# Test_PCB.net
KiCad netlist of a schematic drawn in Altium Designer
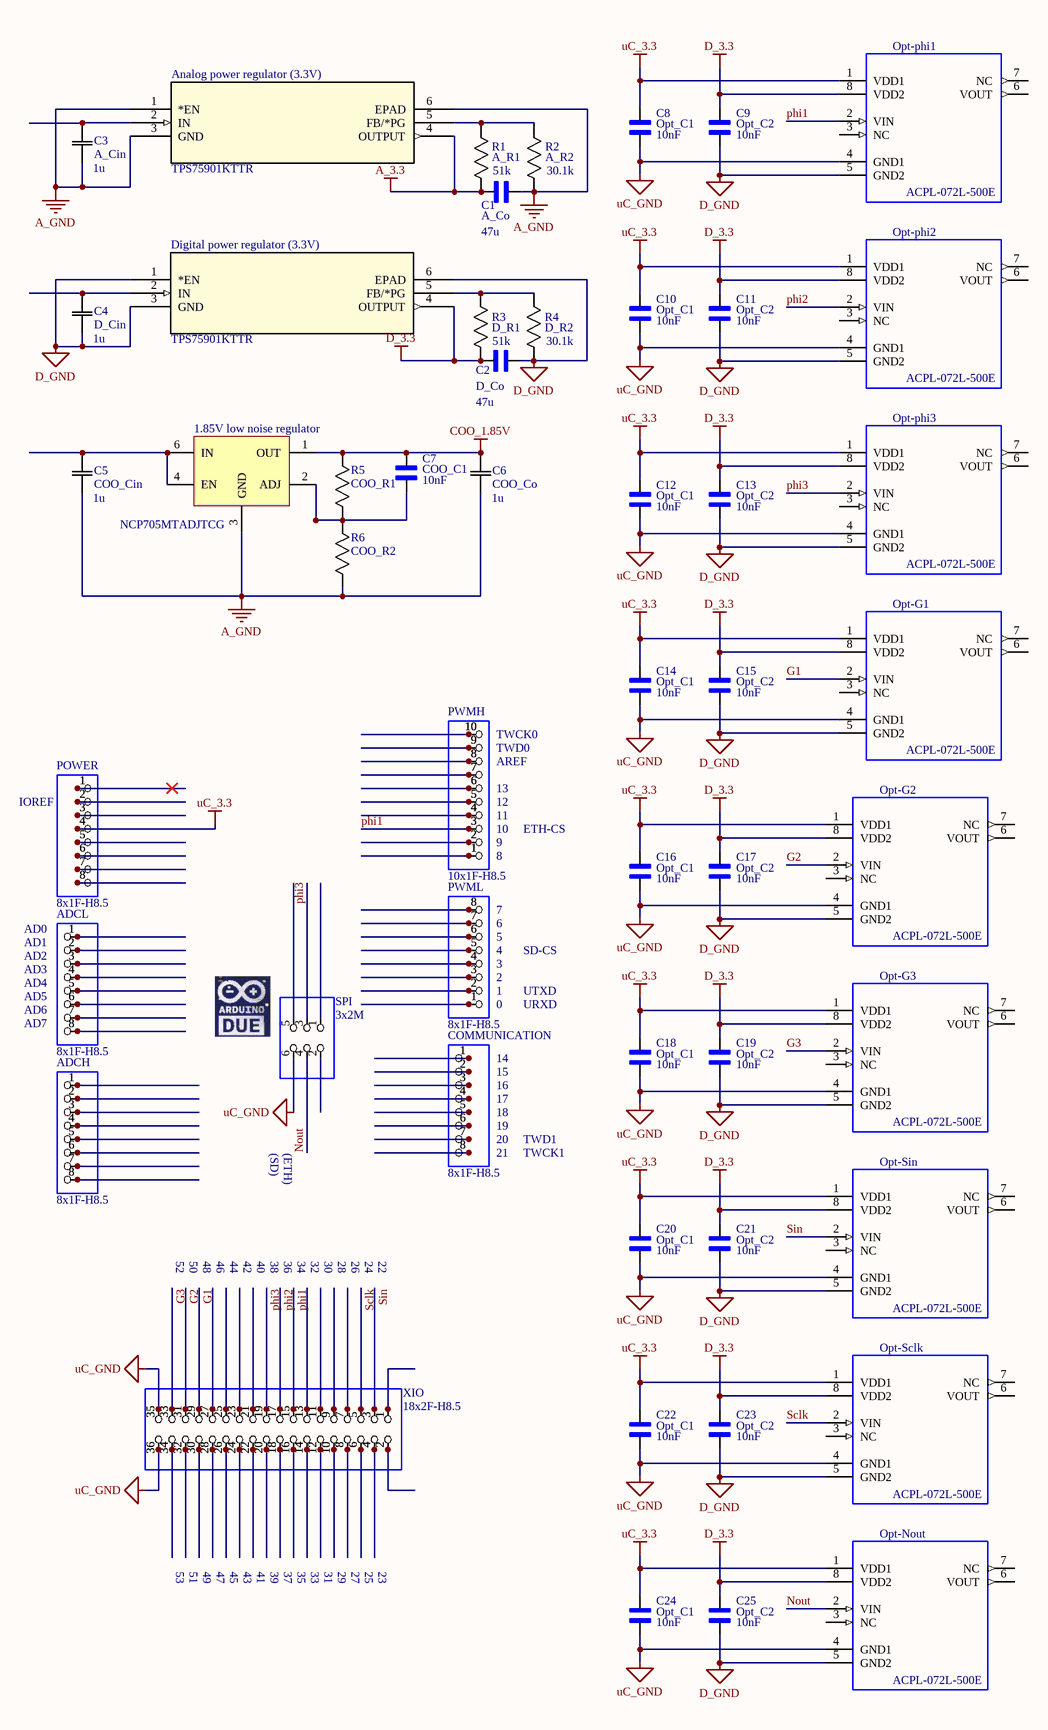
[diagram p0: Test PCB.SchDoc]

(export (version "E")
  (design (tool "Eeschema 10.0.6"))
  (components
    (comp (ref "1.85V low noise regulator")
      (value "NCP705MTADJTCG")
      (footprint "WDFN6")
      (description "500 mA, Ultra-Low  Quiescent Current, IQ 13 A,  Ultra-Low Noise, LDO  Voltage Regulator")
      (fields (field (name "MANUFACTURER") "ON Semiconductor"))
      (libsource (lib "NCP705MTADJTCG") (part "NCP705MTADJTCG"))
    )
    (comp (ref "ADCH") (value "8x1F-H8.5") (footprint "1X08") (libsource (lib "SmartPrj") (part "PINHD-1X8")))
    (comp (ref "ADCL") (value "8x1F-H8.5") (footprint "1X08") (libsource (lib "SmartPrj") (part "PINHD-1X8")))
    (comp (ref "Analog power regulator (3.3V)")
      (value "TPS75901KTTR")
      (footprint "KTT5_6P22X6P86")
      (description "Imported")
      (fields (field (name "MANUFACTURER") "Texas Instruments"))
      (libsource (lib "TPS75901KTTR") (part "TPS75901KTTR"))
    )
    (comp (ref "C1")
      (value "A_Co")
      (footprint "CAPC1608X9N")
      (description "Multilayer Ceramic Capacitors - 47uF 4V X5R 20% Pad SMD 0603 85C T/R")
      (fields
        (field (name "DIGI-KEY_PART_NUMBER") "490-13246-1-ND")
        (field (name "MP") "GRM188R60G476ME15D")
        (field (name "ALTIUM_VALUE") "47u")
      )
      (libsource (lib "47uF 0603  CAP") (part "GRM188R60G476ME15D"))
    )
    (comp (ref "C2")
      (value "D_Co")
      (footprint "CAPC1608X9N")
      (description "Multilayer Ceramic Capacitors - 47uF 4V X5R 20% Pad SMD 0603 85C T/R")
      (fields
        (field (name "DIGI-KEY_PART_NUMBER") "490-13246-1-ND")
        (field (name "MP") "GRM188R60G476ME15D")
        (field (name "ALTIUM_VALUE") "47u")
      )
      (libsource (lib "47uF 0603  CAP") (part "GRM188R60G476ME15D"))
    )
    (comp (ref "C3")
      (value "A_Cin")
      (footprint "CAP_GRM_188")
      (description "Imported")
      (fields
        (field (name "MANUFACTURER_PART_NUMBER") "GRM188R60J105KA01D")
        (field (name "ALTIUM_VALUE") "1u")
      )
      (libsource (lib "1uF 0603 CAP") (part "GRM188R60J105KA0"))
    )
    (comp (ref "C4")
      (value "D_Cin")
      (footprint "CAP_GRM_188")
      (description "Imported")
      (fields
        (field (name "MANUFACTURER_PART_NUMBER") "GRM188R60J105KA01D")
        (field (name "ALTIUM_VALUE") "1u")
      )
      (libsource (lib "1uF 0603 CAP") (part "GRM188R60J105KA0"))
    )
    (comp (ref "C5")
      (value "COO_Cin")
      (footprint "CAP_GRM_188")
      (description "Imported")
      (fields
        (field (name "MANUFACTURER_PART_NUMBER") "GRM188R60J105KA01D")
        (field (name "ALTIUM_VALUE") "1u")
      )
      (libsource (lib "1uF 0603 CAP") (part "GRM188R60J105KA0"))
    )
    (comp (ref "C6")
      (value "COO_Co")
      (footprint "CAP_GRM_188")
      (description "Imported")
      (fields
        (field (name "MANUFACTURER_PART_NUMBER") "GRM188R60J105KA01D")
        (field (name "ALTIUM_VALUE") "1u")
      )
      (libsource (lib "1uF 0603 CAP") (part "GRM188R60J105KA0"))
    )
    (comp (ref "C7")
      (value "COO_C1")
      (footprint "CAPC1608X9N")
      (description "Multilayer Ceramic Capacitor, GRM Series, 0.01 F, 5%, C0G / NP0, 50 V, 0603 [1608 Metric]")
      (fields
        (field (name "MF") "Murata")
        (field (name "DIGI-KEY_PART_NUMBER") "490-9666-1-ND")
        (field (name "ALTIUM_VALUE") "10nF")
      )
      (libsource (lib "10nF 0603 CAP") (part "GRM1885C1H103JA01D"))
    )
    (comp (ref "C8")
      (value "Opt_C1")
      (footprint "CAPC1608X9N")
      (description "Multilayer Ceramic Capacitor, GRM Series, 0.01 F, 5%, C0G / NP0, 50 V, 0603 [1608 Metric]")
      (fields
        (field (name "MF") "Murata")
        (field (name "DIGI-KEY_PART_NUMBER") "490-9666-1-ND")
        (field (name "ALTIUM_VALUE") "10nF")
      )
      (libsource (lib "10nF 0603 CAP") (part "GRM1885C1H103JA01D"))
    )
    (comp (ref "C9")
      (value "Opt_C2")
      (footprint "CAPC1608X9N")
      (description "Multilayer Ceramic Capacitor, GRM Series, 0.01 F, 5%, C0G / NP0, 50 V, 0603 [1608 Metric]")
      (fields
        (field (name "MF") "Murata")
        (field (name "DIGI-KEY_PART_NUMBER") "490-9666-1-ND")
        (field (name "ALTIUM_VALUE") "10nF")
      )
      (libsource (lib "10nF 0603 CAP") (part "GRM1885C1H103JA01D"))
    )
    (comp (ref "C10")
      (value "Opt_C1")
      (footprint "CAPC1608X9N")
      (description "Multilayer Ceramic Capacitor, GRM Series, 0.01 F, 5%, C0G / NP0, 50 V, 0603 [1608 Metric]")
      (fields
        (field (name "MF") "Murata")
        (field (name "DIGI-KEY_PART_NUMBER") "490-9666-1-ND")
        (field (name "ALTIUM_VALUE") "10nF")
      )
      (libsource (lib "10nF 0603 CAP") (part "GRM1885C1H103JA01D"))
    )
    (comp (ref "C11")
      (value "Opt_C2")
      (footprint "CAPC1608X9N")
      (description "Multilayer Ceramic Capacitor, GRM Series, 0.01 F, 5%, C0G / NP0, 50 V, 0603 [1608 Metric]")
      (fields
        (field (name "MF") "Murata")
        (field (name "DIGI-KEY_PART_NUMBER") "490-9666-1-ND")
        (field (name "ALTIUM_VALUE") "10nF")
      )
      (libsource (lib "10nF 0603 CAP") (part "GRM1885C1H103JA01D"))
    )
    (comp (ref "C12")
      (value "Opt_C1")
      (footprint "CAPC1608X9N")
      (description "Multilayer Ceramic Capacitor, GRM Series, 0.01 F, 5%, C0G / NP0, 50 V, 0603 [1608 Metric]")
      (fields
        (field (name "MF") "Murata")
        (field (name "DIGI-KEY_PART_NUMBER") "490-9666-1-ND")
        (field (name "ALTIUM_VALUE") "10nF")
      )
      (libsource (lib "10nF 0603 CAP") (part "GRM1885C1H103JA01D"))
    )
    (comp (ref "C13")
      (value "Opt_C2")
      (footprint "CAPC1608X9N")
      (description "Multilayer Ceramic Capacitor, GRM Series, 0.01 F, 5%, C0G / NP0, 50 V, 0603 [1608 Metric]")
      (fields
        (field (name "MF") "Murata")
        (field (name "DIGI-KEY_PART_NUMBER") "490-9666-1-ND")
        (field (name "ALTIUM_VALUE") "10nF")
      )
      (libsource (lib "10nF 0603 CAP") (part "GRM1885C1H103JA01D"))
    )
    (comp (ref "C14")
      (value "Opt_C1")
      (footprint "CAPC1608X9N")
      (description "Multilayer Ceramic Capacitor, GRM Series, 0.01 F, 5%, C0G / NP0, 50 V, 0603 [1608 Metric]")
      (fields
        (field (name "MF") "Murata")
        (field (name "DIGI-KEY_PART_NUMBER") "490-9666-1-ND")
        (field (name "ALTIUM_VALUE") "10nF")
      )
      (libsource (lib "10nF 0603 CAP") (part "GRM1885C1H103JA01D"))
    )
    (comp (ref "C15")
      (value "Opt_C2")
      (footprint "CAPC1608X9N")
      (description "Multilayer Ceramic Capacitor, GRM Series, 0.01 F, 5%, C0G / NP0, 50 V, 0603 [1608 Metric]")
      (fields
        (field (name "MF") "Murata")
        (field (name "DIGI-KEY_PART_NUMBER") "490-9666-1-ND")
        (field (name "ALTIUM_VALUE") "10nF")
      )
      (libsource (lib "10nF 0603 CAP") (part "GRM1885C1H103JA01D"))
    )
    (comp (ref "C16")
      (value "Opt_C1")
      (footprint "CAPC1608X9N")
      (description "Multilayer Ceramic Capacitor, GRM Series, 0.01 F, 5%, C0G / NP0, 50 V, 0603 [1608 Metric]")
      (fields
        (field (name "MF") "Murata")
        (field (name "DIGI-KEY_PART_NUMBER") "490-9666-1-ND")
        (field (name "ALTIUM_VALUE") "10nF")
      )
      (libsource (lib "10nF 0603 CAP") (part "GRM1885C1H103JA01D"))
    )
    (comp (ref "C17")
      (value "Opt_C2")
      (footprint "CAPC1608X9N")
      (description "Multilayer Ceramic Capacitor, GRM Series, 0.01 F, 5%, C0G / NP0, 50 V, 0603 [1608 Metric]")
      (fields
        (field (name "MF") "Murata")
        (field (name "DIGI-KEY_PART_NUMBER") "490-9666-1-ND")
        (field (name "ALTIUM_VALUE") "10nF")
      )
      (libsource (lib "10nF 0603 CAP") (part "GRM1885C1H103JA01D"))
    )
    (comp (ref "C18")
      (value "Opt_C1")
      (footprint "CAPC1608X9N")
      (description "Multilayer Ceramic Capacitor, GRM Series, 0.01 F, 5%, C0G / NP0, 50 V, 0603 [1608 Metric]")
      (fields
        (field (name "MF") "Murata")
        (field (name "DIGI-KEY_PART_NUMBER") "490-9666-1-ND")
        (field (name "ALTIUM_VALUE") "10nF")
      )
      (libsource (lib "10nF 0603 CAP") (part "GRM1885C1H103JA01D"))
    )
    (comp (ref "C19")
      (value "Opt_C2")
      (footprint "CAPC1608X9N")
      (description "Multilayer Ceramic Capacitor, GRM Series, 0.01 F, 5%, C0G / NP0, 50 V, 0603 [1608 Metric]")
      (fields
        (field (name "MF") "Murata")
        (field (name "DIGI-KEY_PART_NUMBER") "490-9666-1-ND")
        (field (name "ALTIUM_VALUE") "10nF")
      )
      (libsource (lib "10nF 0603 CAP") (part "GRM1885C1H103JA01D"))
    )
    (comp (ref "C20")
      (value "Opt_C1")
      (footprint "CAPC1608X9N")
      (description "Multilayer Ceramic Capacitor, GRM Series, 0.01 F, 5%, C0G / NP0, 50 V, 0603 [1608 Metric]")
      (fields
        (field (name "MF") "Murata")
        (field (name "DIGI-KEY_PART_NUMBER") "490-9666-1-ND")
        (field (name "ALTIUM_VALUE") "10nF")
      )
      (libsource (lib "10nF 0603 CAP") (part "GRM1885C1H103JA01D"))
    )
    (comp (ref "C21")
      (value "Opt_C2")
      (footprint "CAPC1608X9N")
      (description "Multilayer Ceramic Capacitor, GRM Series, 0.01 F, 5%, C0G / NP0, 50 V, 0603 [1608 Metric]")
      (fields
        (field (name "MF") "Murata")
        (field (name "DIGI-KEY_PART_NUMBER") "490-9666-1-ND")
        (field (name "ALTIUM_VALUE") "10nF")
      )
      (libsource (lib "10nF 0603 CAP") (part "GRM1885C1H103JA01D"))
    )
    (comp (ref "C22")
      (value "Opt_C1")
      (footprint "CAPC1608X9N")
      (description "Multilayer Ceramic Capacitor, GRM Series, 0.01 F, 5%, C0G / NP0, 50 V, 0603 [1608 Metric]")
      (fields
        (field (name "MF") "Murata")
        (field (name "DIGI-KEY_PART_NUMBER") "490-9666-1-ND")
        (field (name "ALTIUM_VALUE") "10nF")
      )
      (libsource (lib "10nF 0603 CAP") (part "GRM1885C1H103JA01D"))
    )
    (comp (ref "C23")
      (value "Opt_C2")
      (footprint "CAPC1608X9N")
      (description "Multilayer Ceramic Capacitor, GRM Series, 0.01 F, 5%, C0G / NP0, 50 V, 0603 [1608 Metric]")
      (fields
        (field (name "MF") "Murata")
        (field (name "DIGI-KEY_PART_NUMBER") "490-9666-1-ND")
        (field (name "ALTIUM_VALUE") "10nF")
      )
      (libsource (lib "10nF 0603 CAP") (part "GRM1885C1H103JA01D"))
    )
    (comp (ref "C24")
      (value "Opt_C1")
      (footprint "CAPC1608X9N")
      (description "Multilayer Ceramic Capacitor, GRM Series, 0.01 F, 5%, C0G / NP0, 50 V, 0603 [1608 Metric]")
      (fields
        (field (name "MF") "Murata")
        (field (name "DIGI-KEY_PART_NUMBER") "490-9666-1-ND")
        (field (name "ALTIUM_VALUE") "10nF")
      )
      (libsource (lib "10nF 0603 CAP") (part "GRM1885C1H103JA01D"))
    )
    (comp (ref "C25")
      (value "Opt_C2")
      (footprint "CAPC1608X9N")
      (description "Multilayer Ceramic Capacitor, GRM Series, 0.01 F, 5%, C0G / NP0, 50 V, 0603 [1608 Metric]")
      (fields
        (field (name "MF") "Murata")
        (field (name "DIGI-KEY_PART_NUMBER") "490-9666-1-ND")
        (field (name "ALTIUM_VALUE") "10nF")
      )
      (libsource (lib "10nF 0603 CAP") (part "GRM1885C1H103JA01D"))
    )
    (comp (ref "COMMUNICATION")
      (value "8x1F-H8.5")
      (footprint "1X08")
      (libsource (lib "SmartPrj") (part "PINHD-1X8"))
    )
    (comp (ref "Digital power regulator (3.3V)")
      (value "TPS75901KTTR")
      (footprint "KTT5_6P22X6P86")
      (description "Imported")
      (fields (field (name "MANUFACTURER") "Texas Instruments"))
      (libsource (lib "TPS75901KTTR") (part "TPS75901KTTR"))
    )
    (comp (ref "Opt-G1")
      (value "ACPL-072L-500E")
      (footprint "SOIC127P1150X330-8N")
      (description "Optocoupler Logic-Out Push-Pull Logic, Buffer-IN 1-CH 8-Pin SOIC T/R")
      (fields (field (name "DIGI-KEY_PART_NUMBER") "516-3131-1-ND") (field (name "MF") "Broadcom"))
      (libsource (lib "ACPL-072L-500E") (part "ACPL-072L-500E"))
    )
    (comp (ref "Opt-G2")
      (value "ACPL-072L-500E")
      (footprint "SOIC127P1150X330-8N")
      (description "Optocoupler Logic-Out Push-Pull Logic, Buffer-IN 1-CH 8-Pin SOIC T/R")
      (fields (field (name "DIGI-KEY_PART_NUMBER") "516-3131-1-ND") (field (name "MF") "Broadcom"))
      (libsource (lib "ACPL-072L-500E") (part "ACPL-072L-500E"))
    )
    (comp (ref "Opt-G3")
      (value "ACPL-072L-500E")
      (footprint "SOIC127P1150X330-8N")
      (description "Optocoupler Logic-Out Push-Pull Logic, Buffer-IN 1-CH 8-Pin SOIC T/R")
      (fields (field (name "DIGI-KEY_PART_NUMBER") "516-3131-1-ND") (field (name "MF") "Broadcom"))
      (libsource (lib "ACPL-072L-500E") (part "ACPL-072L-500E"))
    )
    (comp (ref "Opt-Nout")
      (value "ACPL-072L-500E")
      (footprint "SOIC127P1150X330-8N")
      (description "Optocoupler Logic-Out Push-Pull Logic, Buffer-IN 1-CH 8-Pin SOIC T/R")
      (fields (field (name "DIGI-KEY_PART_NUMBER") "516-3131-1-ND") (field (name "MF") "Broadcom"))
      (libsource (lib "ACPL-072L-500E") (part "ACPL-072L-500E"))
    )
    (comp (ref "Opt-phi1")
      (value "ACPL-072L-500E")
      (footprint "SOIC127P1150X330-8N")
      (description "Optocoupler Logic-Out Push-Pull Logic, Buffer-IN 1-CH 8-Pin SOIC T/R")
      (fields (field (name "DIGI-KEY_PART_NUMBER") "516-3131-1-ND") (field (name "MF") "Broadcom"))
      (libsource (lib "ACPL-072L-500E") (part "ACPL-072L-500E"))
    )
    (comp (ref "Opt-phi2")
      (value "ACPL-072L-500E")
      (footprint "SOIC127P1150X330-8N")
      (description "Optocoupler Logic-Out Push-Pull Logic, Buffer-IN 1-CH 8-Pin SOIC T/R")
      (fields (field (name "DIGI-KEY_PART_NUMBER") "516-3131-1-ND") (field (name "MF") "Broadcom"))
      (libsource (lib "ACPL-072L-500E") (part "ACPL-072L-500E"))
    )
    (comp (ref "Opt-phi3")
      (value "ACPL-072L-500E")
      (footprint "SOIC127P1150X330-8N")
      (description "Optocoupler Logic-Out Push-Pull Logic, Buffer-IN 1-CH 8-Pin SOIC T/R")
      (fields (field (name "DIGI-KEY_PART_NUMBER") "516-3131-1-ND") (field (name "MF") "Broadcom"))
      (libsource (lib "ACPL-072L-500E") (part "ACPL-072L-500E"))
    )
    (comp (ref "Opt-Sclk")
      (value "ACPL-072L-500E")
      (footprint "SOIC127P1150X330-8N")
      (description "Optocoupler Logic-Out Push-Pull Logic, Buffer-IN 1-CH 8-Pin SOIC T/R")
      (fields (field (name "DIGI-KEY_PART_NUMBER") "516-3131-1-ND") (field (name "MF") "Broadcom"))
      (libsource (lib "ACPL-072L-500E") (part "ACPL-072L-500E"))
    )
    (comp (ref "Opt-Sin")
      (value "ACPL-072L-500E")
      (footprint "SOIC127P1150X330-8N")
      (description "Optocoupler Logic-Out Push-Pull Logic, Buffer-IN 1-CH 8-Pin SOIC T/R")
      (fields (field (name "DIGI-KEY_PART_NUMBER") "516-3131-1-ND") (field (name "MF") "Broadcom"))
      (libsource (lib "ACPL-072L-500E") (part "ACPL-072L-500E"))
    )
    (comp (ref "POWER")
      (value "8x1F-H8.5")
      (footprint "1X08")
      (libsource (lib "SmartPrj") (part "PINHD-1X8"))
    )
    (comp (ref "PWMH")
      (value "10x1F-H8.5")
      (footprint "1X10")
      (libsource (lib "SmartPrj") (part "PINHD-1X10"))
    )
    (comp (ref "PWML") (value "8x1F-H8.5") (footprint "1X08") (libsource (lib "SmartPrj") (part "PINHD-1X8")))
    (comp (ref "R1")
      (value "A_R1")
      (footprint "RES_0816")
      (description "Imported")
      (fields (field (name "MANUFACTURER_PART_NUMBER") "RR0816P-513-D") (field (name "ALTIUM_VALUE") "51k"))
      (libsource (lib "51kOhm 0603 RES") (part "RR0816P-513-D"))
    )
    (comp (ref "R2")
      (value "A_R2")
      (footprint "RC0603N")
      (description "Imported")
      (fields
        (field (name "MANUFACTURER_PART_NUMBER") "RT0603BRD0730K1L")
        (field (name "ALTIUM_VALUE") "30.1k")
      )
      (libsource (lib "30.1kOhm 0603 RES") (part "RT0603BRD0730K1L"))
    )
    (comp (ref "R3")
      (value "D_R1")
      (footprint "RES_0816")
      (description "Imported")
      (fields (field (name "MANUFACTURER_PART_NUMBER") "RR0816P-513-D") (field (name "ALTIUM_VALUE") "51k"))
      (libsource (lib "51kOhm 0603 RES") (part "RR0816P-513-D"))
    )
    (comp (ref "R4")
      (value "D_R2")
      (footprint "RC0603N")
      (description "Imported")
      (fields
        (field (name "MANUFACTURER_PART_NUMBER") "RT0603BRD0730K1L")
        (field (name "ALTIUM_VALUE") "30.1k")
      )
      (libsource (lib "30.1kOhm 0603 RES") (part "RT0603BRD0730K1L"))
    )
    (comp (ref "R5")
      (value "COO_R1")
      (footprint "RC0603N")
      (description "Imported")
      (fields (field (name "MANUFACTURER_PART_NUMBER") "RC0603FR-07130KL"))
      (libsource (lib "130k 0603 RES") (part "RC0603FR-07130KL"))
    )
    (comp (ref "R6")
      (value "COO_R2")
      (footprint "RC0603N")
      (description "Imported")
      (fields (field (name "MANUFACTURER_PART_NUMBER") "ERJ-3GEY0R00V"))
      (libsource (lib "98.8k 0603 RES") (part "ERJ-3GEY0R00V"))
    )
    (comp (ref "SPI") (value "3x2M") (footprint "2X03") (libsource (lib "SmartPrj") (part "PINHD-2X3")))
    (comp (ref "XIO")
      (value "18x2F-H8.5")
      (footprint "2X18")
      (libsource (lib "SmartPrj") (part "PINHD-2X18"))
    )
  )
  (nets
    (net (code "1") (name "/G1") (class "Default")
      (node (ref "Opt-G1") (pin "2") (pinfunction "VIN_2") (pintype "input"))
      (node (ref "XIO") (pin "29") (pinfunction "29_29") (pintype "passive"))
    )
    (net (code "2") (name "/G2") (class "Default")
      (node (ref "Opt-G2") (pin "2") (pinfunction "VIN_2") (pintype "input"))
      (node (ref "XIO") (pin "31") (pinfunction "31_31") (pintype "passive"))
    )
    (net (code "3") (name "/G3") (class "Default")
      (node (ref "Opt-G3") (pin "2") (pinfunction "VIN_2") (pintype "input"))
      (node (ref "XIO") (pin "33") (pinfunction "33_33") (pintype "passive"))
    )
    (net (code "4") (name "/Nout") (class "Default")
      (node (ref "Opt-Nout") (pin "2") (pinfunction "VIN_2") (pintype "input"))
      (node (ref "SPI") (pin "4") (pinfunction "4_4") (pintype "passive"))
    )
    (net (code "5") (name "/Sclk") (class "Default")
      (node (ref "Opt-Sclk") (pin "2") (pinfunction "VIN_2") (pintype "input"))
      (node (ref "XIO") (pin "5") (pinfunction "5_5") (pintype "passive"))
    )
    (net (code "6") (name "/Sin") (class "Default")
      (node (ref "Opt-Sin") (pin "2") (pinfunction "VIN_2") (pintype "input"))
      (node (ref "XIO") (pin "3") (pinfunction "3_3") (pintype "passive"))
    )
    (net (code "7") (name "/phi1") (class "Default")
      (node (ref "Opt-phi1") (pin "2") (pinfunction "VIN_2") (pintype "input"))
      (node (ref "PWMH") (pin "3") (pinfunction "3_3") (pintype "passive"))
      (node (ref "XIO") (pin "15") (pinfunction "15_15") (pintype "passive"))
    )
    (net (code "8") (name "/phi2") (class "Default")
      (node (ref "Opt-phi2") (pin "2") (pinfunction "VIN_2") (pintype "input"))
      (node (ref "XIO") (pin "17") (pinfunction "17_17") (pintype "passive"))
    )
    (net (code "9") (name "/phi3") (class "Default")
      (node (ref "Opt-phi3") (pin "2") (pinfunction "VIN_2") (pintype "input"))
      (node (ref "SPI") (pin "3") (pinfunction "3_3") (pintype "passive"))
      (node (ref "XIO") (pin "19") (pinfunction "19_19") (pintype "passive"))
    )
    (net (code "10") (name "A_3.3") (class "Default")
      (node (ref "Analog power regulator (3.3V)") (pin "4") (pinfunction "OUTPUT_4") (pintype "output"))
      (node (ref "C1") (pin "2") (pinfunction "2_2") (pintype "passive"))
      (node (ref "R1") (pin "1") (pinfunction "1_1") (pintype "passive"))
    )
    (net (code "11") (name "A_GND") (class "Default")
      (node (ref "1.85V low noise regulator") (pin "3") (pinfunction "GND_3") (pintype "passive"))
      (node (ref "Analog power regulator (3.3V)") (pin "1") (pinfunction "*EN_1") (pintype "passive"))
      (node (ref "Analog power regulator (3.3V)") (pin "3") (pinfunction "GND_3") (pintype "power_in"))
      (node (ref "Analog power regulator (3.3V)") (pin "6") (pinfunction "EPAD_6") (pintype "passive"))
      (node (ref "C1") (pin "1") (pinfunction "1_1") (pintype "passive"))
      (node (ref "C3") (pin "1") (pinfunction "1_1") (pintype "passive"))
      (node (ref "C5") (pin "1") (pinfunction "1_1") (pintype "passive"))
      (node (ref "C6") (pin "1") (pinfunction "1_1") (pintype "passive"))
      (node (ref "R2") (pin "2") (pinfunction "2_2") (pintype "passive"))
      (node (ref "R6") (pin "2") (pinfunction "2_2") (pintype "passive"))
    )
    (net (code "12") (name "COO_1.85V") (class "Default")
      (node (ref "1.85V low noise regulator") (pin "1") (pinfunction "OUT_1") (pintype "passive"))
      (node (ref "C6") (pin "2") (pinfunction "2_2") (pintype "passive"))
      (node (ref "C7") (pin "1") (pinfunction "1_1") (pintype "passive"))
      (node (ref "R5") (pin "1") (pinfunction "1_1") (pintype "passive"))
    )
    (net (code "13") (name "D_3.3") (class "Default")
      (node (ref "C11") (pin "1") (pinfunction "1_1") (pintype "passive"))
      (node (ref "C13") (pin "1") (pinfunction "1_1") (pintype "passive"))
      (node (ref "C15") (pin "1") (pinfunction "1_1") (pintype "passive"))
      (node (ref "C17") (pin "1") (pinfunction "1_1") (pintype "passive"))
      (node (ref "C19") (pin "1") (pinfunction "1_1") (pintype "passive"))
      (node (ref "C2") (pin "2") (pinfunction "2_2") (pintype "passive"))
      (node (ref "C21") (pin "1") (pinfunction "1_1") (pintype "passive"))
      (node (ref "C23") (pin "1") (pinfunction "1_1") (pintype "passive"))
      (node (ref "C25") (pin "1") (pinfunction "1_1") (pintype "passive"))
      (node (ref "C9") (pin "1") (pinfunction "1_1") (pintype "passive"))
      (node (ref "Digital power regulator (3.3V)") (pin "4") (pinfunction "OUTPUT_4") (pintype "output"))
      (node (ref "Opt-G1") (pin "8") (pinfunction "VDD2_8") (pintype "power_in"))
      (node (ref "Opt-G2") (pin "8") (pinfunction "VDD2_8") (pintype "power_in"))
      (node (ref "Opt-G3") (pin "8") (pinfunction "VDD2_8") (pintype "power_in"))
      (node (ref "Opt-Nout") (pin "8") (pinfunction "VDD2_8") (pintype "power_in"))
      (node (ref "Opt-Sclk") (pin "8") (pinfunction "VDD2_8") (pintype "power_in"))
      (node (ref "Opt-Sin") (pin "8") (pinfunction "VDD2_8") (pintype "power_in"))
      (node (ref "Opt-phi1") (pin "8") (pinfunction "VDD2_8") (pintype "power_in"))
      (node (ref "Opt-phi2") (pin "8") (pinfunction "VDD2_8") (pintype "power_in"))
      (node (ref "Opt-phi3") (pin "8") (pinfunction "VDD2_8") (pintype "power_in"))
      (node (ref "R3") (pin "1") (pinfunction "1_1") (pintype "passive"))
    )
    (net (code "14") (name "D_GND") (class "Default")
      (node (ref "C11") (pin "2") (pinfunction "2_2") (pintype "passive"))
      (node (ref "C13") (pin "2") (pinfunction "2_2") (pintype "passive"))
      (node (ref "C15") (pin "2") (pinfunction "2_2") (pintype "passive"))
      (node (ref "C17") (pin "2") (pinfunction "2_2") (pintype "passive"))
      (node (ref "C19") (pin "2") (pinfunction "2_2") (pintype "passive"))
      (node (ref "C2") (pin "1") (pinfunction "1_1") (pintype "passive"))
      (node (ref "C21") (pin "2") (pinfunction "2_2") (pintype "passive"))
      (node (ref "C23") (pin "2") (pinfunction "2_2") (pintype "passive"))
      (node (ref "C25") (pin "2") (pinfunction "2_2") (pintype "passive"))
      (node (ref "C4") (pin "1") (pinfunction "1_1") (pintype "passive"))
      (node (ref "C9") (pin "2") (pinfunction "2_2") (pintype "passive"))
      (node (ref "Digital power regulator (3.3V)") (pin "1") (pinfunction "*EN_1") (pintype "passive"))
      (node (ref "Digital power regulator (3.3V)") (pin "3") (pinfunction "GND_3") (pintype "power_in"))
      (node (ref "Digital power regulator (3.3V)") (pin "6") (pinfunction "EPAD_6") (pintype "passive"))
      (node (ref "Opt-G1") (pin "5") (pinfunction "GND2_5") (pintype "passive"))
      (node (ref "Opt-G2") (pin "5") (pinfunction "GND2_5") (pintype "passive"))
      (node (ref "Opt-G3") (pin "5") (pinfunction "GND2_5") (pintype "passive"))
      (node (ref "Opt-Nout") (pin "5") (pinfunction "GND2_5") (pintype "passive"))
      (node (ref "Opt-Sclk") (pin "5") (pinfunction "GND2_5") (pintype "passive"))
      (node (ref "Opt-Sin") (pin "5") (pinfunction "GND2_5") (pintype "passive"))
      (node (ref "Opt-phi1") (pin "5") (pinfunction "GND2_5") (pintype "passive"))
      (node (ref "Opt-phi2") (pin "5") (pinfunction "GND2_5") (pintype "passive"))
      (node (ref "Opt-phi3") (pin "5") (pinfunction "GND2_5") (pintype "passive"))
      (node (ref "R4") (pin "2") (pinfunction "2_2") (pintype "passive"))
    )
    (net (code "15") (name "Net-(1.85V low noise regulator-ADJ)") (class "Default")
      (node (ref "1.85V low noise regulator") (pin "2") (pinfunction "ADJ_2") (pintype "passive"))
      (node (ref "C7") (pin "2") (pinfunction "2_2") (pintype "passive"))
      (node (ref "R5") (pin "2") (pinfunction "2_2") (pintype "passive"))
      (node (ref "R6") (pin "1") (pinfunction "1_1") (pintype "passive"))
    )
    (net (code "16") (name "Net-(1.85V low noise regulator-EN)") (class "Default")
      (node (ref "1.85V low noise regulator") (pin "4") (pinfunction "EN_4") (pintype "passive"))
      (node (ref "1.85V low noise regulator") (pin "6") (pinfunction "IN_6") (pintype "passive"))
      (node (ref "C5") (pin "2") (pinfunction "2_2") (pintype "passive"))
    )
    (net (code "17") (name "Net-(ADCH-Pad1)") (class "Default")
      (node (ref "ADCH") (pin "1") (pinfunction "1_1") (pintype "passive"))
    )
    (net (code "18") (name "Net-(ADCH-Pad2)") (class "Default")
      (node (ref "ADCH") (pin "2") (pinfunction "2_2") (pintype "passive"))
    )
    (net (code "19") (name "Net-(ADCH-Pad3)") (class "Default")
      (node (ref "ADCH") (pin "3") (pinfunction "3_3") (pintype "passive"))
    )
    (net (code "20") (name "Net-(ADCH-Pad4)") (class "Default")
      (node (ref "ADCH") (pin "4") (pinfunction "4_4") (pintype "passive"))
    )
    (net (code "21") (name "Net-(ADCH-Pad5)") (class "Default")
      (node (ref "ADCH") (pin "5") (pinfunction "5_5") (pintype "passive"))
    )
    (net (code "22") (name "Net-(ADCH-Pad6)") (class "Default")
      (node (ref "ADCH") (pin "6") (pinfunction "6_6") (pintype "passive"))
    )
    (net (code "23") (name "Net-(ADCH-Pad7)") (class "Default")
      (node (ref "ADCH") (pin "7") (pinfunction "7_7") (pintype "passive"))
    )
    (net (code "24") (name "Net-(ADCH-Pad8)") (class "Default")
      (node (ref "ADCH") (pin "8") (pinfunction "8_8") (pintype "passive"))
    )
    (net (code "25") (name "Net-(ADCL-Pad1)") (class "Default")
      (node (ref "ADCL") (pin "1") (pinfunction "1_1") (pintype "passive"))
    )
    (net (code "26") (name "Net-(ADCL-Pad2)") (class "Default")
      (node (ref "ADCL") (pin "2") (pinfunction "2_2") (pintype "passive"))
    )
    (net (code "27") (name "Net-(ADCL-Pad3)") (class "Default")
      (node (ref "ADCL") (pin "3") (pinfunction "3_3") (pintype "passive"))
    )
    (net (code "28") (name "Net-(ADCL-Pad4)") (class "Default")
      (node (ref "ADCL") (pin "4") (pinfunction "4_4") (pintype "passive"))
    )
    (net (code "29") (name "Net-(ADCL-Pad5)") (class "Default")
      (node (ref "ADCL") (pin "5") (pinfunction "5_5") (pintype "passive"))
    )
    (net (code "30") (name "Net-(ADCL-Pad6)") (class "Default")
      (node (ref "ADCL") (pin "6") (pinfunction "6_6") (pintype "passive"))
    )
    (net (code "31") (name "Net-(ADCL-Pad7)") (class "Default")
      (node (ref "ADCL") (pin "7") (pinfunction "7_7") (pintype "passive"))
    )
    (net (code "32") (name "Net-(ADCL-Pad8)") (class "Default")
      (node (ref "ADCL") (pin "8") (pinfunction "8_8") (pintype "passive"))
    )
    (net (code "33") (name "Net-(Analog power regulator (3.3V)-FB{slash}*PG)") (class "Default")
      (node (ref "Analog power regulator (3.3V)") (pin "5") (pinfunction "FB/*PG_5") (pintype "passive"))
      (node (ref "R1") (pin "2") (pinfunction "2_2") (pintype "passive"))
      (node (ref "R2") (pin "1") (pinfunction "1_1") (pintype "passive"))
    )
    (net (code "34") (name "Net-(Analog power regulator (3.3V)-IN)") (class "Default")
      (node (ref "Analog power regulator (3.3V)") (pin "2") (pinfunction "IN_2") (pintype "input"))
      (node (ref "C3") (pin "2") (pinfunction "2_2") (pintype "passive"))
    )
    (net (code "35") (name "Net-(COMMUNICATION-Pad1)") (class "Default")
      (node (ref "COMMUNICATION") (pin "1") (pinfunction "1_1") (pintype "passive"))
    )
    (net (code "36") (name "Net-(COMMUNICATION-Pad2)") (class "Default")
      (node (ref "COMMUNICATION") (pin "2") (pinfunction "2_2") (pintype "passive"))
    )
    (net (code "37") (name "Net-(COMMUNICATION-Pad3)") (class "Default")
      (node (ref "COMMUNICATION") (pin "3") (pinfunction "3_3") (pintype "passive"))
    )
    (net (code "38") (name "Net-(COMMUNICATION-Pad4)") (class "Default")
      (node (ref "COMMUNICATION") (pin "4") (pinfunction "4_4") (pintype "passive"))
    )
    (net (code "39") (name "Net-(COMMUNICATION-Pad5)") (class "Default")
      (node (ref "COMMUNICATION") (pin "5") (pinfunction "5_5") (pintype "passive"))
    )
    (net (code "40") (name "Net-(COMMUNICATION-Pad6)") (class "Default")
      (node (ref "COMMUNICATION") (pin "6") (pinfunction "6_6") (pintype "passive"))
    )
    (net (code "41") (name "Net-(COMMUNICATION-Pad7)") (class "Default")
      (node (ref "COMMUNICATION") (pin "7") (pinfunction "7_7") (pintype "passive"))
    )
    (net (code "42") (name "Net-(COMMUNICATION-Pad8)") (class "Default")
      (node (ref "COMMUNICATION") (pin "8") (pinfunction "8_8") (pintype "passive"))
    )
    (net (code "43") (name "Net-(Digital power regulator (3.3V)-FB{slash}*PG)") (class "Default")
      (node (ref "Digital power regulator (3.3V)") (pin "5") (pinfunction "FB/*PG_5") (pintype "passive"))
      (node (ref "R3") (pin "2") (pinfunction "2_2") (pintype "passive"))
      (node (ref "R4") (pin "1") (pinfunction "1_1") (pintype "passive"))
    )
    (net (code "44") (name "Net-(Digital power regulator (3.3V)-IN)") (class "Default")
      (node (ref "C4") (pin "2") (pinfunction "2_2") (pintype "passive"))
      (node (ref "Digital power regulator (3.3V)") (pin "2") (pinfunction "IN_2") (pintype "input"))
    )
    (net (code "45") (name "Net-(POWER-Pad1)") (class "Default")
      (node (ref "POWER") (pin "1") (pinfunction "1_1") (pintype "passive"))
    )
    (net (code "46") (name "Net-(POWER-Pad2)") (class "Default")
      (node (ref "POWER") (pin "2") (pinfunction "2_2") (pintype "passive"))
    )
    (net (code "47") (name "Net-(POWER-Pad3)") (class "Default")
      (node (ref "POWER") (pin "3") (pinfunction "3_3") (pintype "passive"))
    )
    (net (code "48") (name "Net-(POWER-Pad5)") (class "Default")
      (node (ref "POWER") (pin "5") (pinfunction "5_5") (pintype "passive"))
    )
    (net (code "49") (name "Net-(POWER-Pad6)") (class "Default")
      (node (ref "POWER") (pin "6") (pinfunction "6_6") (pintype "passive"))
    )
    (net (code "50") (name "Net-(POWER-Pad7)") (class "Default")
      (node (ref "POWER") (pin "7") (pinfunction "7_7") (pintype "passive"))
    )
    (net (code "51") (name "Net-(POWER-Pad8)") (class "Default")
      (node (ref "POWER") (pin "8") (pinfunction "8_8") (pintype "passive"))
    )
    (net (code "52") (name "Net-(PWMH-Pad1)") (class "Default")
      (node (ref "PWMH") (pin "1") (pinfunction "1_1") (pintype "passive"))
    )
    (net (code "53") (name "Net-(PWMH-Pad2)") (class "Default")
      (node (ref "PWMH") (pin "2") (pinfunction "2_2") (pintype "passive"))
    )
    (net (code "54") (name "Net-(PWMH-Pad4)") (class "Default")
      (node (ref "PWMH") (pin "4") (pinfunction "4_4") (pintype "passive"))
    )
    (net (code "55") (name "Net-(PWMH-Pad5)") (class "Default")
      (node (ref "PWMH") (pin "5") (pinfunction "5_5") (pintype "passive"))
    )
    (net (code "56") (name "Net-(PWMH-Pad6)") (class "Default")
      (node (ref "PWMH") (pin "6") (pinfunction "6_6") (pintype "passive"))
    )
    (net (code "57") (name "Net-(PWMH-Pad7)") (class "Default")
      (node (ref "PWMH") (pin "7") (pinfunction "7_7") (pintype "passive"))
    )
    (net (code "58") (name "Net-(PWMH-Pad8)") (class "Default")
      (node (ref "PWMH") (pin "8") (pinfunction "8_8") (pintype "passive"))
    )
    (net (code "59") (name "Net-(PWMH-Pad9)") (class "Default")
      (node (ref "PWMH") (pin "9") (pinfunction "9_9") (pintype "passive"))
    )
    (net (code "60") (name "Net-(PWMH-Pad10)") (class "Default")
      (node (ref "PWMH") (pin "10") (pinfunction "10_10") (pintype "passive"))
    )
    (net (code "61") (name "Net-(PWML-Pad1)") (class "Default")
      (node (ref "PWML") (pin "1") (pinfunction "1_1") (pintype "passive"))
    )
    (net (code "62") (name "Net-(PWML-Pad2)") (class "Default")
      (node (ref "PWML") (pin "2") (pinfunction "2_2") (pintype "passive"))
    )
    (net (code "63") (name "Net-(PWML-Pad3)") (class "Default")
      (node (ref "PWML") (pin "3") (pinfunction "3_3") (pintype "passive"))
    )
    (net (code "64") (name "Net-(PWML-Pad4)") (class "Default")
      (node (ref "PWML") (pin "4") (pinfunction "4_4") (pintype "passive"))
    )
    (net (code "65") (name "Net-(PWML-Pad5)") (class "Default")
      (node (ref "PWML") (pin "5") (pinfunction "5_5") (pintype "passive"))
    )
    (net (code "66") (name "Net-(PWML-Pad6)") (class "Default")
      (node (ref "PWML") (pin "6") (pinfunction "6_6") (pintype "passive"))
    )
    (net (code "67") (name "Net-(PWML-Pad7)") (class "Default")
      (node (ref "PWML") (pin "7") (pinfunction "7_7") (pintype "passive"))
    )
    (net (code "68") (name "Net-(PWML-Pad8)") (class "Default")
      (node (ref "PWML") (pin "8") (pinfunction "8_8") (pintype "passive"))
    )
    (net (code "69") (name "Net-(XIO-Pad1)") (class "Default")
      (node (ref "XIO") (pin "1") (pinfunction "1_1") (pintype "passive"))
    )
    (net (code "70") (name "Net-(XIO-Pad2)") (class "Default")
      (node (ref "XIO") (pin "2") (pinfunction "2_2") (pintype "passive"))
    )
    (net (code "71") (name "Net-(XIO-Pad4)") (class "Default")
      (node (ref "XIO") (pin "4") (pinfunction "4_4") (pintype "passive"))
    )
    (net (code "72") (name "Net-(XIO-Pad6)") (class "Default")
      (node (ref "XIO") (pin "6") (pinfunction "6_6") (pintype "passive"))
    )
    (net (code "73") (name "Net-(XIO-Pad7)") (class "Default")
      (node (ref "XIO") (pin "7") (pinfunction "7_7") (pintype "passive"))
    )
    (net (code "74") (name "Net-(XIO-Pad8)") (class "Default")
      (node (ref "XIO") (pin "8") (pinfunction "8_8") (pintype "passive"))
    )
    (net (code "75") (name "Net-(XIO-Pad9)") (class "Default")
      (node (ref "XIO") (pin "9") (pinfunction "9_9") (pintype "passive"))
    )
    (net (code "76") (name "Net-(XIO-Pad10)") (class "Default")
      (node (ref "XIO") (pin "10") (pinfunction "10_10") (pintype "passive"))
    )
    (net (code "77") (name "Net-(XIO-Pad11)") (class "Default")
      (node (ref "XIO") (pin "11") (pinfunction "11_11") (pintype "passive"))
    )
    (net (code "78") (name "Net-(XIO-Pad12)") (class "Default")
      (node (ref "XIO") (pin "12") (pinfunction "12_12") (pintype "passive"))
    )
    (net (code "79") (name "Net-(XIO-Pad13)") (class "Default")
      (node (ref "XIO") (pin "13") (pinfunction "13_13") (pintype "passive"))
    )
    (net (code "80") (name "Net-(XIO-Pad14)") (class "Default")
      (node (ref "XIO") (pin "14") (pinfunction "14_14") (pintype "passive"))
    )
    (net (code "81") (name "Net-(XIO-Pad16)") (class "Default")
      (node (ref "XIO") (pin "16") (pinfunction "16_16") (pintype "passive"))
    )
    (net (code "82") (name "Net-(XIO-Pad18)") (class "Default")
      (node (ref "XIO") (pin "18") (pinfunction "18_18") (pintype "passive"))
    )
    (net (code "83") (name "Net-(XIO-Pad20)") (class "Default")
      (node (ref "XIO") (pin "20") (pinfunction "20_20") (pintype "passive"))
    )
    (net (code "84") (name "Net-(XIO-Pad21)") (class "Default")
      (node (ref "XIO") (pin "21") (pinfunction "21_21") (pintype "passive"))
    )
    (net (code "85") (name "Net-(XIO-Pad22)") (class "Default")
      (node (ref "XIO") (pin "22") (pinfunction "22_22") (pintype "passive"))
    )
    (net (code "86") (name "Net-(XIO-Pad23)") (class "Default")
      (node (ref "XIO") (pin "23") (pinfunction "23_23") (pintype "passive"))
    )
    (net (code "87") (name "Net-(XIO-Pad24)") (class "Default")
      (node (ref "XIO") (pin "24") (pinfunction "24_24") (pintype "passive"))
    )
    (net (code "88") (name "Net-(XIO-Pad25)") (class "Default")
      (node (ref "XIO") (pin "25") (pinfunction "25_25") (pintype "passive"))
    )
    (net (code "89") (name "Net-(XIO-Pad26)") (class "Default")
      (node (ref "XIO") (pin "26") (pinfunction "26_26") (pintype "passive"))
    )
    (net (code "90") (name "Net-(XIO-Pad27)") (class "Default")
      (node (ref "XIO") (pin "27") (pinfunction "27_27") (pintype "passive"))
    )
    (net (code "91") (name "Net-(XIO-Pad28)") (class "Default")
      (node (ref "XIO") (pin "28") (pinfunction "28_28") (pintype "passive"))
    )
    (net (code "92") (name "Net-(XIO-Pad30)") (class "Default")
      (node (ref "XIO") (pin "30") (pinfunction "30_30") (pintype "passive"))
    )
    (net (code "93") (name "Net-(XIO-Pad32)") (class "Default")
      (node (ref "XIO") (pin "32") (pinfunction "32_32") (pintype "passive"))
    )
    (net (code "94") (name "Net-(XIO-Pad34)") (class "Default")
      (node (ref "XIO") (pin "34") (pinfunction "34_34") (pintype "passive"))
    )
    (net (code "95") (name "uC_3.3") (class "Default")
      (node (ref "C10") (pin "1") (pinfunction "1_1") (pintype "passive"))
      (node (ref "C12") (pin "1") (pinfunction "1_1") (pintype "passive"))
      (node (ref "C14") (pin "1") (pinfunction "1_1") (pintype "passive"))
      (node (ref "C16") (pin "1") (pinfunction "1_1") (pintype "passive"))
      (node (ref "C18") (pin "1") (pinfunction "1_1") (pintype "passive"))
      (node (ref "C20") (pin "1") (pinfunction "1_1") (pintype "passive"))
      (node (ref "C22") (pin "1") (pinfunction "1_1") (pintype "passive"))
      (node (ref "C24") (pin "1") (pinfunction "1_1") (pintype "passive"))
      (node (ref "C8") (pin "1") (pinfunction "1_1") (pintype "passive"))
      (node (ref "Opt-G1") (pin "1") (pinfunction "VDD1_1") (pintype "power_in"))
      (node (ref "Opt-G2") (pin "1") (pinfunction "VDD1_1") (pintype "power_in"))
      (node (ref "Opt-G3") (pin "1") (pinfunction "VDD1_1") (pintype "power_in"))
      (node (ref "Opt-Nout") (pin "1") (pinfunction "VDD1_1") (pintype "power_in"))
      (node (ref "Opt-Sclk") (pin "1") (pinfunction "VDD1_1") (pintype "power_in"))
      (node (ref "Opt-Sin") (pin "1") (pinfunction "VDD1_1") (pintype "power_in"))
      (node (ref "Opt-phi1") (pin "1") (pinfunction "VDD1_1") (pintype "power_in"))
      (node (ref "Opt-phi2") (pin "1") (pinfunction "VDD1_1") (pintype "power_in"))
      (node (ref "Opt-phi3") (pin "1") (pinfunction "VDD1_1") (pintype "power_in"))
      (node (ref "POWER") (pin "4") (pinfunction "4_4") (pintype "passive"))
    )
    (net (code "96") (name "uC_GND") (class "Default")
      (node (ref "C10") (pin "2") (pinfunction "2_2") (pintype "passive"))
      (node (ref "C12") (pin "2") (pinfunction "2_2") (pintype "passive"))
      (node (ref "C14") (pin "2") (pinfunction "2_2") (pintype "passive"))
      (node (ref "C16") (pin "2") (pinfunction "2_2") (pintype "passive"))
      (node (ref "C18") (pin "2") (pinfunction "2_2") (pintype "passive"))
      (node (ref "C20") (pin "2") (pinfunction "2_2") (pintype "passive"))
      (node (ref "C22") (pin "2") (pinfunction "2_2") (pintype "passive"))
      (node (ref "C24") (pin "2") (pinfunction "2_2") (pintype "passive"))
      (node (ref "C8") (pin "2") (pinfunction "2_2") (pintype "passive"))
      (node (ref "Opt-G1") (pin "4") (pinfunction "GND1_4") (pintype "passive"))
      (node (ref "Opt-G2") (pin "4") (pinfunction "GND1_4") (pintype "passive"))
      (node (ref "Opt-G3") (pin "4") (pinfunction "GND1_4") (pintype "passive"))
      (node (ref "Opt-Nout") (pin "4") (pinfunction "GND1_4") (pintype "passive"))
      (node (ref "Opt-Sclk") (pin "4") (pinfunction "GND1_4") (pintype "passive"))
      (node (ref "Opt-Sin") (pin "4") (pinfunction "GND1_4") (pintype "passive"))
      (node (ref "Opt-phi1") (pin "4") (pinfunction "GND1_4") (pintype "passive"))
      (node (ref "Opt-phi2") (pin "4") (pinfunction "GND1_4") (pintype "passive"))
      (node (ref "Opt-phi3") (pin "4") (pinfunction "GND1_4") (pintype "passive"))
      (node (ref "SPI") (pin "6") (pinfunction "6_6") (pintype "passive"))
      (node (ref "XIO") (pin "35") (pinfunction "35_35") (pintype "passive"))
      (node (ref "XIO") (pin "36") (pinfunction "36_36") (pintype "passive"))
    )
    (net (code "97") (name "unconnected-(Opt-G1-NC-Pad3)") (class "Default")
      (node (ref "Opt-G1") (pin "3") (pinfunction "NC_3") (pintype "input"))
    )
    (net (code "98") (name "unconnected-(Opt-G1-NC-Pad7)") (class "Default")
      (node (ref "Opt-G1") (pin "7") (pinfunction "NC_7") (pintype "output"))
    )
    (net (code "99") (name "unconnected-(Opt-G1-VOUT-Pad6)") (class "Default")
      (node (ref "Opt-G1") (pin "6") (pinfunction "VOUT_6") (pintype "output"))
    )
    (net (code "100") (name "unconnected-(Opt-G2-NC-Pad3)") (class "Default")
      (node (ref "Opt-G2") (pin "3") (pinfunction "NC_3") (pintype "input"))
    )
    (net (code "101") (name "unconnected-(Opt-G2-NC-Pad7)") (class "Default")
      (node (ref "Opt-G2") (pin "7") (pinfunction "NC_7") (pintype "output"))
    )
    (net (code "102") (name "unconnected-(Opt-G2-VOUT-Pad6)") (class "Default")
      (node (ref "Opt-G2") (pin "6") (pinfunction "VOUT_6") (pintype "output"))
    )
    (net (code "103") (name "unconnected-(Opt-G3-NC-Pad3)") (class "Default")
      (node (ref "Opt-G3") (pin "3") (pinfunction "NC_3") (pintype "input"))
    )
    (net (code "104") (name "unconnected-(Opt-G3-NC-Pad7)") (class "Default")
      (node (ref "Opt-G3") (pin "7") (pinfunction "NC_7") (pintype "output"))
    )
    (net (code "105") (name "unconnected-(Opt-G3-VOUT-Pad6)") (class "Default")
      (node (ref "Opt-G3") (pin "6") (pinfunction "VOUT_6") (pintype "output"))
    )
    (net (code "106") (name "unconnected-(Opt-Nout-NC-Pad3)") (class "Default")
      (node (ref "Opt-Nout") (pin "3") (pinfunction "NC_3") (pintype "input"))
    )
    (net (code "107") (name "unconnected-(Opt-Nout-NC-Pad7)") (class "Default")
      (node (ref "Opt-Nout") (pin "7") (pinfunction "NC_7") (pintype "output"))
    )
    (net (code "108") (name "unconnected-(Opt-Nout-VOUT-Pad6)") (class "Default")
      (node (ref "Opt-Nout") (pin "6") (pinfunction "VOUT_6") (pintype "output"))
    )
    (net (code "109") (name "unconnected-(Opt-Sclk-NC-Pad3)") (class "Default")
      (node (ref "Opt-Sclk") (pin "3") (pinfunction "NC_3") (pintype "input"))
    )
    (net (code "110") (name "unconnected-(Opt-Sclk-NC-Pad7)") (class "Default")
      (node (ref "Opt-Sclk") (pin "7") (pinfunction "NC_7") (pintype "output"))
    )
    (net (code "111") (name "unconnected-(Opt-Sclk-VOUT-Pad6)") (class "Default")
      (node (ref "Opt-Sclk") (pin "6") (pinfunction "VOUT_6") (pintype "output"))
    )
    (net (code "112") (name "unconnected-(Opt-Sin-NC-Pad3)") (class "Default")
      (node (ref "Opt-Sin") (pin "3") (pinfunction "NC_3") (pintype "input"))
    )
    (net (code "113") (name "unconnected-(Opt-Sin-NC-Pad7)") (class "Default")
      (node (ref "Opt-Sin") (pin "7") (pinfunction "NC_7") (pintype "output"))
    )
    (net (code "114") (name "unconnected-(Opt-Sin-VOUT-Pad6)") (class "Default")
      (node (ref "Opt-Sin") (pin "6") (pinfunction "VOUT_6") (pintype "output"))
    )
    (net (code "115") (name "unconnected-(Opt-phi1-NC-Pad3)") (class "Default")
      (node (ref "Opt-phi1") (pin "3") (pinfunction "NC_3") (pintype "input"))
    )
    (net (code "116") (name "unconnected-(Opt-phi1-NC-Pad7)") (class "Default")
      (node (ref "Opt-phi1") (pin "7") (pinfunction "NC_7") (pintype "output"))
    )
    (net (code "117") (name "unconnected-(Opt-phi1-VOUT-Pad6)") (class "Default")
      (node (ref "Opt-phi1") (pin "6") (pinfunction "VOUT_6") (pintype "output"))
    )
    (net (code "118") (name "unconnected-(Opt-phi2-NC-Pad3)") (class "Default")
      (node (ref "Opt-phi2") (pin "3") (pinfunction "NC_3") (pintype "input"))
    )
    (net (code "119") (name "unconnected-(Opt-phi2-NC-Pad7)") (class "Default")
      (node (ref "Opt-phi2") (pin "7") (pinfunction "NC_7") (pintype "output"))
    )
    (net (code "120") (name "unconnected-(Opt-phi2-VOUT-Pad6)") (class "Default")
      (node (ref "Opt-phi2") (pin "6") (pinfunction "VOUT_6") (pintype "output"))
    )
    (net (code "121") (name "unconnected-(Opt-phi3-NC-Pad3)") (class "Default")
      (node (ref "Opt-phi3") (pin "3") (pinfunction "NC_3") (pintype "input"))
    )
    (net (code "122") (name "unconnected-(Opt-phi3-NC-Pad7)") (class "Default")
      (node (ref "Opt-phi3") (pin "7") (pinfunction "NC_7") (pintype "output"))
    )
    (net (code "123") (name "unconnected-(Opt-phi3-VOUT-Pad6)") (class "Default")
      (node (ref "Opt-phi3") (pin "6") (pinfunction "VOUT_6") (pintype "output"))
    )
    (net (code "124") (name "unconnected-(SPI-Pad1)") (class "Default")
      (node (ref "SPI") (pin "1") (pinfunction "1_1") (pintype "passive"))
    )
    (net (code "125") (name "unconnected-(SPI-Pad2)") (class "Default")
      (node (ref "SPI") (pin "2") (pinfunction "2_2") (pintype "passive"))
    )
    (net (code "126") (name "unconnected-(SPI-Pad5)") (class "Default")
      (node (ref "SPI") (pin "5") (pinfunction "5_5") (pintype "passive"))
    )
  )
)
